# P04_AUDIO_RGB.net
KiCad netlist of a schematic drawn in EasyEDA
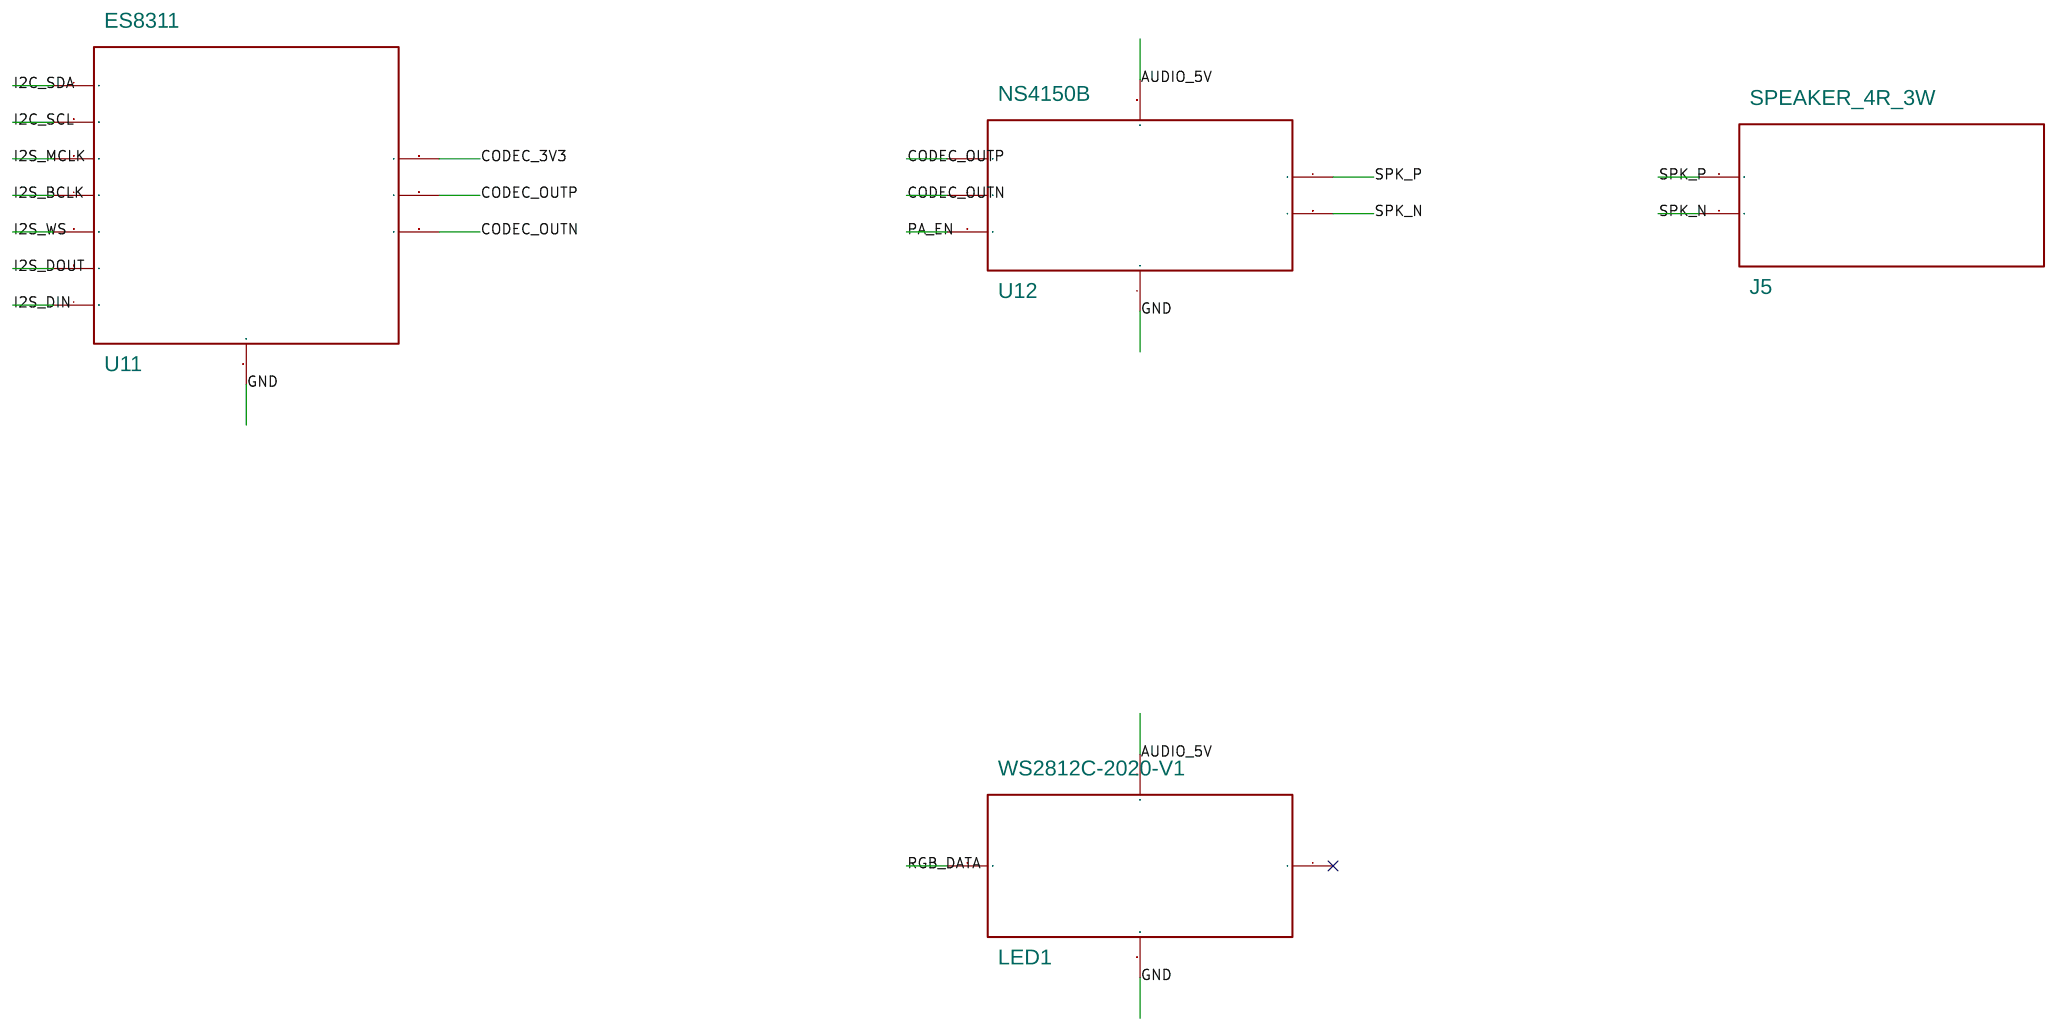
[diagram p0: schematic sheet]

(export (version "E")
  (design (tool "Eeschema 10.0.6"))
  (components
    (comp (ref "J5") (value "SPEAKER_4R_3W") (libsource (lib "") (part "Speaker")))
    (comp (ref "LED1") (value "WS2812C-2020-V1") (libsource (lib "") (part "WS2812C")))
    (comp (ref "U11") (value "ES8311") (libsource (lib "") (part "ES8311")))
    (comp (ref "U12") (value "NS4150B") (libsource (lib "") (part "NS4150B")))
  )
  (nets
    (net (code "1") (name "/AUDIO_5V") (class "Default")
      (node (ref "LED1") (pin "2") (pinfunction "1_2") (pintype "unspecified"))
      (node (ref "U12") (pin "6") (pinfunction "1_6") (pintype "unspecified"))
    )
    (net (code "2") (name "/CODEC_3V3") (class "Default")
      (node (ref "U11") (pin "8") (pinfunction "1_8") (pintype "unspecified"))
    )
    (net (code "3") (name "/CODEC_OUTN") (class "Default")
      (node (ref "U11") (pin "10") (pinfunction "1_10") (pintype "unspecified"))
      (node (ref "U12") (pin "2") (pinfunction "1_2") (pintype "unspecified"))
    )
    (net (code "4") (name "/CODEC_OUTP") (class "Default")
      (node (ref "U11") (pin "9") (pinfunction "1_9") (pintype "unspecified"))
      (node (ref "U12") (pin "1") (pinfunction "1_1") (pintype "unspecified"))
    )
    (net (code "5") (name "/GND") (class "Default")
      (node (ref "LED1") (pin "3") (pinfunction "1_3") (pintype "unspecified"))
      (node (ref "U11") (pin "11") (pinfunction "1_11") (pintype "unspecified"))
      (node (ref "U12") (pin "7") (pinfunction "1_7") (pintype "unspecified"))
    )
    (net (code "6") (name "/I2C_SCL") (class "Default")
      (node (ref "U11") (pin "2") (pinfunction "1_2") (pintype "unspecified"))
    )
    (net (code "7") (name "/I2C_SDA") (class "Default")
      (node (ref "U11") (pin "1") (pinfunction "1_1") (pintype "unspecified"))
    )
    (net (code "8") (name "/I2S_BCLK") (class "Default")
      (node (ref "U11") (pin "4") (pinfunction "1_4") (pintype "unspecified"))
    )
    (net (code "9") (name "/I2S_DIN") (class "Default")
      (node (ref "U11") (pin "7") (pinfunction "1_7") (pintype "unspecified"))
    )
    (net (code "10") (name "/I2S_DOUT") (class "Default")
      (node (ref "U11") (pin "6") (pinfunction "1_6") (pintype "unspecified"))
    )
    (net (code "11") (name "/I2S_MCLK") (class "Default")
      (node (ref "U11") (pin "3") (pinfunction "1_3") (pintype "unspecified"))
    )
    (net (code "12") (name "/I2S_WS") (class "Default")
      (node (ref "U11") (pin "5") (pinfunction "1_5") (pintype "unspecified"))
    )
    (net (code "13") (name "/PA_EN") (class "Default")
      (node (ref "U12") (pin "3") (pinfunction "1_3") (pintype "unspecified"))
    )
    (net (code "14") (name "/RGB_DATA") (class "Default")
      (node (ref "LED1") (pin "1") (pinfunction "1_1") (pintype "unspecified"))
    )
    (net (code "15") (name "/SPK_N") (class "Default")
      (node (ref "J5") (pin "2") (pinfunction "1_2") (pintype "unspecified"))
      (node (ref "U12") (pin "5") (pinfunction "1_5") (pintype "unspecified"))
    )
    (net (code "16") (name "/SPK_P") (class "Default")
      (node (ref "J5") (pin "1") (pinfunction "1_1") (pintype "unspecified"))
      (node (ref "U12") (pin "4") (pinfunction "1_4") (pintype "unspecified"))
    )
    (net (code "17") (name "unconnected-(LED1-1-Pad4)") (class "Default")
      (node (ref "LED1") (pin "4") (pinfunction "1_4") (pintype "unspecified+no_connect"))
    )
  )
)
